# MCU.net
KiCad netlist of a schematic drawn in Altium Designer
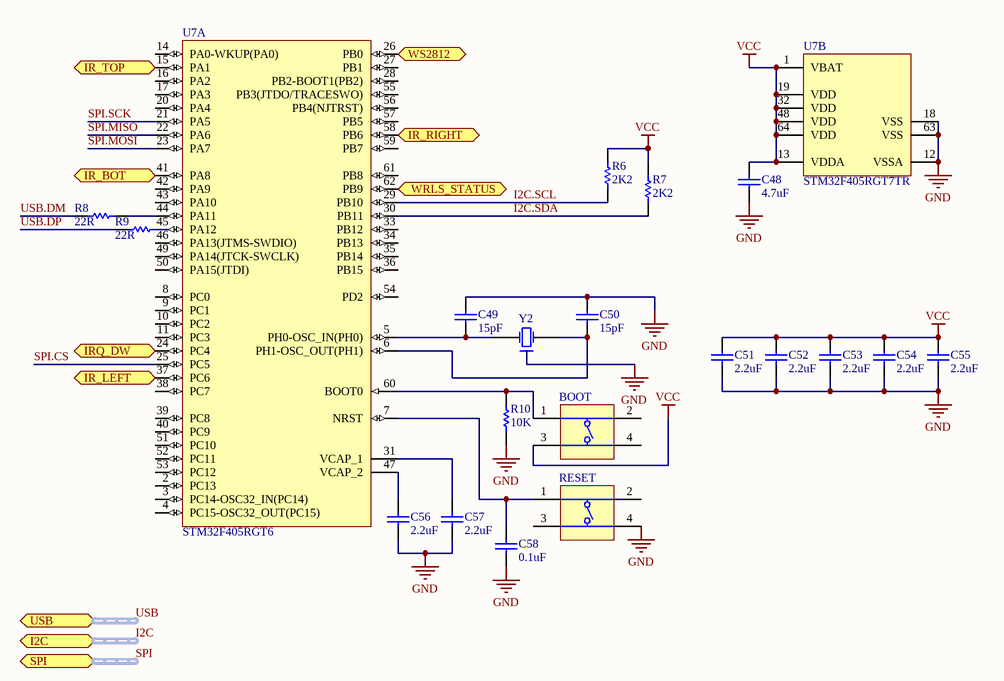
[diagram p0: MCU.SchDoc]

(export (version "E")
  (design (tool "Eeschema 10.0.6"))
  (components
    (comp (ref "BOOT")
      (value "~")
      (footprint "SWITCH")
      (description "Switch, SPNO Push Button SMD")
      (fields
        (field (name "MANUFACTURER") "C&K Components")
        (field (name "PARTNUMBER") "PTS810 SJM 250 SMTR LFS")
      )
      (libsource (lib "Components") (part "DIPT-DTSM-6"))
    )
    (comp (ref "C48")
      (value "4.7uF")
      (footprint "C0402[1005X55]")
      (description "4.7uF 6.3V 20% 0402 (1005 Metric)")
      (fields (field (name "TOLERANCE") "20%") (field (name "PARTNUMBER") "GRM155R60J475ME47D"))
      (libsource (lib "Capacitors") (part "CAP_4.7uF_6.3V_0402_20%"))
    )
    (comp (ref "C49")
      (value "15pF")
      (footprint "C0402[1005X55]")
      (description "15pF 50V 5% 0402 (1005 Metric)")
      (fields (field (name "TOLERANCE") "5%") (field (name "PARTNUMBER") "GRM1555C1H150JA01D"))
      (libsource (lib "Capacitors") (part "CAP_15pF_50V_0402_5%"))
    )
    (comp (ref "C50")
      (value "15pF")
      (footprint "C0402[1005X55]")
      (description "15pF 50V 5% 0402 (1005 Metric)")
      (fields (field (name "TOLERANCE") "5%") (field (name "PARTNUMBER") "GRM1555C1H150JA01D"))
      (libsource (lib "Capacitors") (part "CAP_15pF_50V_0402_5%"))
    )
    (comp (ref "C51")
      (value "2.2uF")
      (footprint "C0402[1005X55]")
      (description "2.2uF 6.3V 20% 0402 (1005 Metric)")
      (fields (field (name "TOLERANCE") "20%") (field (name "PARTNUMBER") "GRM155R60J225ME15D"))
      (libsource (lib "Capacitors") (part "CAP_2.2uF_6.3V_0402_20%"))
    )
    (comp (ref "C52")
      (value "2.2uF")
      (footprint "C0402[1005X55]")
      (description "2.2uF 6.3V 20% 0402 (1005 Metric)")
      (fields (field (name "TOLERANCE") "20%") (field (name "PARTNUMBER") "GRM155R60J225ME15D"))
      (libsource (lib "Capacitors") (part "CAP_2.2uF_6.3V_0402_20%"))
    )
    (comp (ref "C53")
      (value "2.2uF")
      (footprint "C0402[1005X55]")
      (description "2.2uF 6.3V 20% 0402 (1005 Metric)")
      (fields (field (name "TOLERANCE") "20%") (field (name "PARTNUMBER") "GRM155R60J225ME15D"))
      (libsource (lib "Capacitors") (part "CAP_2.2uF_6.3V_0402_20%"))
    )
    (comp (ref "C54")
      (value "2.2uF")
      (footprint "C0402[1005X55]")
      (description "2.2uF 6.3V 20% 0402 (1005 Metric)")
      (fields (field (name "TOLERANCE") "20%") (field (name "PARTNUMBER") "GRM155R60J225ME15D"))
      (libsource (lib "Capacitors") (part "CAP_2.2uF_6.3V_0402_20%"))
    )
    (comp (ref "C55")
      (value "2.2uF")
      (footprint "C0402[1005X55]")
      (description "2.2uF 6.3V 20% 0402 (1005 Metric)")
      (fields (field (name "TOLERANCE") "20%") (field (name "PARTNUMBER") "GRM155R60J225ME15D"))
      (libsource (lib "Capacitors") (part "CAP_2.2uF_6.3V_0402_20%"))
    )
    (comp (ref "C56")
      (value "2.2uF")
      (footprint "C0402[1005X55]")
      (description "2.2uF 6.3V 20% 0402 (1005 Metric)")
      (fields (field (name "TOLERANCE") "20%") (field (name "PARTNUMBER") "GRM155R60J225ME15D"))
      (libsource (lib "Capacitors") (part "CAP_2.2uF_6.3V_0402_20%"))
    )
    (comp (ref "C57")
      (value "2.2uF")
      (footprint "C0402[1005X55]")
      (description "2.2uF 6.3V 20% 0402 (1005 Metric)")
      (fields (field (name "TOLERANCE") "20%") (field (name "PARTNUMBER") "GRM155R60J225ME15D"))
      (libsource (lib "Capacitors") (part "CAP_2.2uF_6.3V_0402_20%"))
    )
    (comp (ref "C58")
      (value "0.1uF")
      (footprint "C0402[1005X55]")
      (description "0.1uF 6.3V 10% 0402 (1005 Metric)")
      (fields (field (name "TOLERANCE") "10%") (field (name "PARTNUMBER") "GRM155R70J104KA01D"))
      (libsource (lib "Capacitors") (part "CAP_0.1uF_6.3V_0402_10%"))
    )
    (comp (ref "R6")
      (value "2K2")
      (footprint "R0402[1005]")
      (description "2K2 0.063W 1% 0402 (1005 Metric)")
      (fields (field (name "TOLERANCE") "1%") (field (name "POWER") "0.063W"))
      (libsource (lib "Resistors") (part "RES_2K2_0402_1%"))
    )
    (comp (ref "R7")
      (value "2K2")
      (footprint "R0402[1005]")
      (description "2K2 0.063W 1% 0402 (1005 Metric)")
      (fields (field (name "TOLERANCE") "1%") (field (name "POWER") "0.063W"))
      (libsource (lib "Resistors") (part "RES_2K2_0402_1%"))
    )
    (comp (ref "R8")
      (value "22R")
      (footprint "R0402[1005]")
      (description "22R 0.063W 1% 0402 (1005 Metric)")
      (fields (field (name "POWER") "0.063W") (field (name "TOLERANCE") "1%"))
      (libsource (lib "Resistors") (part "RES_22R_0402_1%"))
    )
    (comp (ref "R9")
      (value "22R")
      (footprint "R0402[1005]")
      (description "22R 0.063W 1% 0402 (1005 Metric)")
      (fields (field (name "POWER") "0.063W") (field (name "TOLERANCE") "1%"))
      (libsource (lib "Resistors") (part "RES_22R_0402_1%"))
    )
    (comp (ref "R10")
      (value "10K")
      (footprint "R0402[1005]")
      (description "10K 0.063W 1% 0402 (1005 Metric)")
      (fields (field (name "TOLERANCE") "1%") (field (name "POWER") "0.063W"))
      (libsource (lib "Resistors") (part "RES_10K_0402_1%"))
    )
    (comp (ref "RESET")
      (value "~")
      (footprint "SWITCH")
      (description "Switch, SPNO Push Button SMD")
      (fields
        (field (name "MANUFACTURER") "C&K Components")
        (field (name "PARTNUMBER") "PTS810 SJM 250 SMTR LFS")
      )
      (libsource (lib "Components") (part "DIPT-DTSM-6"))
    )
    (comp (ref "U7")
      (value "STM32F405RGT7TR")
      (footprint "STM-LQFP64_V")
      (fields (field (name "MANUFACTURER") "STMicroelectronics"))
      (libsource (lib "Altium Content Vault") (part "CMP-0243-00089-2"))
    )
    (comp (ref "Y2")
      (value "~")
      (footprint "ABRA-ABM3B-4_V")
      (fields (field (name "PARTNUMBER") "ABM3B-8.000MHZ-10-1UT") (field (name "MANUFACTURER") "ABRACON"))
      (libsource (lib "Components") (part "ABRA-ABM3B-4"))
    )
  )
  (nets
    (net (code "4") (name "/I2C.SCL") (class "Default")
      (node (ref "R6") (pin "1") (pinfunction "1_1") (pintype "passive"))
      (node (ref "U7") (pin "29") (pinfunction "PB10_29") (pintype "bidirectional"))
    )
    (net (code "5") (name "/I2C.SDA") (class "Default")
      (node (ref "R7") (pin "1") (pinfunction "1_1") (pintype "passive"))
      (node (ref "U7") (pin "30") (pinfunction "PB11_30") (pintype "bidirectional"))
    )
    (net (code "6") (name "/IRQ_DW") (class "Default")
      (node (ref "U7") (pin "24") (pinfunction "PC4_24") (pintype "bidirectional"))
    )
    (net (code "7") (name "/IR_BOT") (class "Default")
      (node (ref "U7") (pin "41") (pinfunction "PA8_41") (pintype "bidirectional"))
    )
    (net (code "8") (name "/IR_LEFT") (class "Default")
      (node (ref "U7") (pin "37") (pinfunction "PC6_37") (pintype "bidirectional"))
    )
    (net (code "9") (name "/IR_RIGHT") (class "Default")
      (node (ref "U7") (pin "58") (pinfunction "PB6_58") (pintype "bidirectional"))
    )
    (net (code "10") (name "/IR_TOP") (class "Default")
      (node (ref "U7") (pin "15") (pinfunction "PA1_15") (pintype "bidirectional"))
    )
    (net (code "11") (name "/SPI.CS") (class "Default")
      (node (ref "U7") (pin "25") (pinfunction "PC5_25") (pintype "bidirectional"))
    )
    (net (code "12") (name "/SPI.MISO") (class "Default")
      (node (ref "U7") (pin "22") (pinfunction "PA6_22") (pintype "bidirectional"))
    )
    (net (code "13") (name "/SPI.MOSI") (class "Default")
      (node (ref "U7") (pin "23") (pinfunction "PA7_23") (pintype "bidirectional"))
    )
    (net (code "14") (name "/SPI.SCK") (class "Default")
      (node (ref "U7") (pin "21") (pinfunction "PA5_21") (pintype "bidirectional"))
    )
    (net (code "15") (name "/USB.DM") (class "Default")
      (node (ref "R8") (pin "1") (pinfunction "1_1") (pintype "passive"))
    )
    (net (code "16") (name "/USB.DP") (class "Default")
      (node (ref "R9") (pin "1") (pinfunction "1_1") (pintype "passive"))
    )
    (net (code "17") (name "/WRLS_STATUS") (class "Default")
      (node (ref "U7") (pin "62") (pinfunction "PB9_62") (pintype "bidirectional"))
    )
    (net (code "18") (name "/WS2812") (class "Default")
      (node (ref "U7") (pin "26") (pinfunction "PB0_26") (pintype "bidirectional"))
    )
    (net (code "22") (name "GND") (class "Default")
      (node (ref "C48") (pin "1") (pinfunction "1_1") (pintype "passive"))
      (node (ref "C49") (pin "2") (pinfunction "2_2") (pintype "passive"))
      (node (ref "C50") (pin "2") (pinfunction "2_2") (pintype "passive"))
      (node (ref "C51") (pin "1") (pinfunction "1_1") (pintype "passive"))
      (node (ref "C52") (pin "1") (pinfunction "1_1") (pintype "passive"))
      (node (ref "C53") (pin "1") (pinfunction "1_1") (pintype "passive"))
      (node (ref "C54") (pin "1") (pinfunction "1_1") (pintype "passive"))
      (node (ref "C55") (pin "1") (pinfunction "1_1") (pintype "passive"))
      (node (ref "C56") (pin "1") (pinfunction "1_1") (pintype "passive"))
      (node (ref "C57") (pin "1") (pinfunction "1_1") (pintype "passive"))
      (node (ref "C58") (pin "1") (pinfunction "1_1") (pintype "passive"))
      (node (ref "R10") (pin "1") (pinfunction "1_1") (pintype "passive"))
      (node (ref "RESET") (pin "4") (pinfunction "T3_4") (pintype "passive"))
      (node (ref "U7") (pin "12") (pinfunction "VSSA_12") (pintype "power_in"))
      (node (ref "U7") (pin "18") (pinfunction "VSS_18") (pintype "power_in"))
      (node (ref "U7") (pin "63") (pinfunction "VSS_63") (pintype "power_in"))
      (node (ref "Y2") (pin "2") (pinfunction "2_2") (pintype "passive"))
    )
    (net (code "23") (name "Net-(BOOT-T1)") (class "Default")
      (node (ref "BOOT") (pin "1") (pinfunction "T1_1") (pintype "passive"))
      (node (ref "R10") (pin "2") (pinfunction "2_2") (pintype "passive"))
      (node (ref "U7") (pin "60") (pinfunction "BOOT0_60") (pintype "input"))
    )
    (net (code "24") (name "Net-(RESET-T1)") (class "Default")
      (node (ref "C58") (pin "2") (pinfunction "2_2") (pintype "passive"))
      (node (ref "RESET") (pin "1") (pinfunction "T1_1") (pintype "passive"))
      (node (ref "U7") (pin "7") (pinfunction "NRST_7") (pintype "bidirectional"))
    )
    (net (code "25") (name "Net-(U7A-PA11)") (class "Default")
      (node (ref "R8") (pin "2") (pinfunction "2_2") (pintype "passive"))
      (node (ref "U7") (pin "44") (pinfunction "PA11_44") (pintype "bidirectional"))
    )
    (net (code "26") (name "Net-(U7A-PA12)") (class "Default")
      (node (ref "R9") (pin "2") (pinfunction "2_2") (pintype "passive"))
      (node (ref "U7") (pin "45") (pinfunction "PA12_45") (pintype "bidirectional"))
    )
    (net (code "27") (name "Net-(U7A-PH0-OSC_IN(PH0))") (class "Default")
      (node (ref "C49") (pin "1") (pinfunction "1_1") (pintype "passive"))
      (node (ref "U7") (pin "5") (pinfunction "PH0-OSC_IN(PH0)_5") (pintype "bidirectional"))
      (node (ref "Y2") (pin "3") (pinfunction "X2_3") (pintype "passive"))
    )
    (net (code "28") (name "Net-(U7A-PH1-OSC_OUT(PH1))") (class "Default")
      (node (ref "C50") (pin "1") (pinfunction "1_1") (pintype "passive"))
      (node (ref "U7") (pin "6") (pinfunction "PH1-OSC_OUT(PH1)_6") (pintype "bidirectional"))
      (node (ref "Y2") (pin "1") (pinfunction "X1_1") (pintype "passive"))
    )
    (net (code "29") (name "Net-(U7A-VCAP_1)") (class "Default")
      (node (ref "C57") (pin "2") (pinfunction "2_2") (pintype "passive"))
      (node (ref "U7") (pin "31") (pinfunction "VCAP_1_31") (pintype "power_in"))
    )
    (net (code "30") (name "Net-(U7A-VCAP_2)") (class "Default")
      (node (ref "C56") (pin "2") (pinfunction "2_2") (pintype "passive"))
      (node (ref "U7") (pin "47") (pinfunction "VCAP_2_47") (pintype "power_in"))
    )
    (net (code "31") (name "VCC") (class "Default")
      (node (ref "BOOT") (pin "3") (pinfunction "T3_3") (pintype "passive"))
      (node (ref "C48") (pin "2") (pinfunction "2_2") (pintype "passive"))
      (node (ref "C51") (pin "2") (pinfunction "2_2") (pintype "passive"))
      (node (ref "C52") (pin "2") (pinfunction "2_2") (pintype "passive"))
      (node (ref "C53") (pin "2") (pinfunction "2_2") (pintype "passive"))
      (node (ref "C54") (pin "2") (pinfunction "2_2") (pintype "passive"))
      (node (ref "C55") (pin "2") (pinfunction "2_2") (pintype "passive"))
      (node (ref "R6") (pin "2") (pinfunction "2_2") (pintype "passive"))
      (node (ref "R7") (pin "2") (pinfunction "2_2") (pintype "passive"))
      (node (ref "U7") (pin "1") (pinfunction "VBAT_1") (pintype "power_in"))
      (node (ref "U7") (pin "13") (pinfunction "VDDA_13") (pintype "power_in"))
      (node (ref "U7") (pin "19") (pinfunction "VDD_19") (pintype "power_in"))
      (node (ref "U7") (pin "32") (pinfunction "VDD_32") (pintype "power_in"))
      (node (ref "U7") (pin "48") (pinfunction "VDD_48") (pintype "power_in"))
      (node (ref "U7") (pin "64") (pinfunction "VDD_64") (pintype "power_in"))
    )
    (net (code "32") (name "unconnected-(BOOT-T2-Pad2)") (class "Default")
      (node (ref "BOOT") (pin "2") (pinfunction "T2_2") (pintype "passive"))
    )
    (net (code "33") (name "unconnected-(BOOT-T3-Pad4)") (class "Default")
      (node (ref "BOOT") (pin "4") (pinfunction "T3_4") (pintype "passive"))
    )
    (net (code "34") (name "unconnected-(RESET-T2-Pad2)") (class "Default")
      (node (ref "RESET") (pin "2") (pinfunction "T2_2") (pintype "passive"))
    )
    (net (code "35") (name "unconnected-(RESET-T3-Pad3)") (class "Default")
      (node (ref "RESET") (pin "3") (pinfunction "T3_3") (pintype "passive"))
    )
    (net (code "36") (name "unconnected-(U7A-PA0-WKUP(PA0)-Pad14)") (class "Default")
      (node (ref "U7") (pin "14") (pinfunction "PA0-WKUP(PA0)_14") (pintype "bidirectional"))
    )
    (net (code "37") (name "unconnected-(U7A-PA2-Pad16)") (class "Default")
      (node (ref "U7") (pin "16") (pinfunction "PA2_16") (pintype "bidirectional"))
    )
    (net (code "38") (name "unconnected-(U7A-PA3-Pad17)") (class "Default")
      (node (ref "U7") (pin "17") (pinfunction "PA3_17") (pintype "bidirectional"))
    )
    (net (code "39") (name "unconnected-(U7A-PA4-Pad20)") (class "Default")
      (node (ref "U7") (pin "20") (pinfunction "PA4_20") (pintype "bidirectional"))
    )
    (net (code "40") (name "unconnected-(U7A-PA9-Pad42)") (class "Default")
      (node (ref "U7") (pin "42") (pinfunction "PA9_42") (pintype "bidirectional"))
    )
    (net (code "41") (name "unconnected-(U7A-PA10-Pad43)") (class "Default")
      (node (ref "U7") (pin "43") (pinfunction "PA10_43") (pintype "bidirectional"))
    )
    (net (code "42") (name "unconnected-(U7A-PA13(JTMS-SWDIO)-Pad46)") (class "Default")
      (node (ref "U7") (pin "46") (pinfunction "PA13(JTMS-SWDIO)_46") (pintype "bidirectional"))
    )
    (net (code "43") (name "unconnected-(U7A-PA14(JTCK-SWCLK)-Pad49)") (class "Default")
      (node (ref "U7") (pin "49") (pinfunction "PA14(JTCK-SWCLK)_49") (pintype "bidirectional"))
    )
    (net (code "44") (name "unconnected-(U7A-PA15(JTDI)-Pad50)") (class "Default")
      (node (ref "U7") (pin "50") (pinfunction "PA15(JTDI)_50") (pintype "bidirectional"))
    )
    (net (code "45") (name "unconnected-(U7A-PB1-Pad27)") (class "Default")
      (node (ref "U7") (pin "27") (pinfunction "PB1_27") (pintype "bidirectional"))
    )
    (net (code "46") (name "unconnected-(U7A-PB2-BOOT1(PB2)-Pad28)") (class "Default")
      (node (ref "U7") (pin "28") (pinfunction "PB2-BOOT1(PB2)_28") (pintype "bidirectional"))
    )
    (net (code "47") (name "unconnected-(U7A-PB3(JTDO{slash}TRACESWO)-Pad55)") (class "Default")
      (node (ref "U7") (pin "55") (pinfunction "PB3(JTDO/TRACESWO)_55") (pintype "bidirectional"))
    )
    (net (code "48") (name "unconnected-(U7A-PB4(NJTRST)-Pad56)") (class "Default")
      (node (ref "U7") (pin "56") (pinfunction "PB4(NJTRST)_56") (pintype "bidirectional"))
    )
    (net (code "49") (name "unconnected-(U7A-PB5-Pad57)") (class "Default")
      (node (ref "U7") (pin "57") (pinfunction "PB5_57") (pintype "bidirectional"))
    )
    (net (code "50") (name "unconnected-(U7A-PB7-Pad59)") (class "Default")
      (node (ref "U7") (pin "59") (pinfunction "PB7_59") (pintype "bidirectional"))
    )
    (net (code "51") (name "unconnected-(U7A-PB8-Pad61)") (class "Default")
      (node (ref "U7") (pin "61") (pinfunction "PB8_61") (pintype "bidirectional"))
    )
    (net (code "52") (name "unconnected-(U7A-PB12-Pad33)") (class "Default")
      (node (ref "U7") (pin "33") (pinfunction "PB12_33") (pintype "bidirectional"))
    )
    (net (code "53") (name "unconnected-(U7A-PB13-Pad34)") (class "Default")
      (node (ref "U7") (pin "34") (pinfunction "PB13_34") (pintype "bidirectional"))
    )
    (net (code "54") (name "unconnected-(U7A-PB14-Pad35)") (class "Default")
      (node (ref "U7") (pin "35") (pinfunction "PB14_35") (pintype "bidirectional"))
    )
    (net (code "55") (name "unconnected-(U7A-PB15-Pad36)") (class "Default")
      (node (ref "U7") (pin "36") (pinfunction "PB15_36") (pintype "bidirectional"))
    )
    (net (code "56") (name "unconnected-(U7A-PC0-Pad8)") (class "Default")
      (node (ref "U7") (pin "8") (pinfunction "PC0_8") (pintype "bidirectional"))
    )
    (net (code "57") (name "unconnected-(U7A-PC1-Pad9)") (class "Default")
      (node (ref "U7") (pin "9") (pinfunction "PC1_9") (pintype "bidirectional"))
    )
    (net (code "58") (name "unconnected-(U7A-PC2-Pad10)") (class "Default")
      (node (ref "U7") (pin "10") (pinfunction "PC2_10") (pintype "bidirectional"))
    )
    (net (code "59") (name "unconnected-(U7A-PC3-Pad11)") (class "Default")
      (node (ref "U7") (pin "11") (pinfunction "PC3_11") (pintype "bidirectional"))
    )
    (net (code "60") (name "unconnected-(U7A-PC7-Pad38)") (class "Default")
      (node (ref "U7") (pin "38") (pinfunction "PC7_38") (pintype "bidirectional"))
    )
    (net (code "61") (name "unconnected-(U7A-PC8-Pad39)") (class "Default")
      (node (ref "U7") (pin "39") (pinfunction "PC8_39") (pintype "bidirectional"))
    )
    (net (code "62") (name "unconnected-(U7A-PC9-Pad40)") (class "Default")
      (node (ref "U7") (pin "40") (pinfunction "PC9_40") (pintype "bidirectional"))
    )
    (net (code "63") (name "unconnected-(U7A-PC10-Pad51)") (class "Default")
      (node (ref "U7") (pin "51") (pinfunction "PC10_51") (pintype "bidirectional"))
    )
    (net (code "64") (name "unconnected-(U7A-PC11-Pad52)") (class "Default")
      (node (ref "U7") (pin "52") (pinfunction "PC11_52") (pintype "bidirectional"))
    )
    (net (code "65") (name "unconnected-(U7A-PC12-Pad53)") (class "Default")
      (node (ref "U7") (pin "53") (pinfunction "PC12_53") (pintype "bidirectional"))
    )
    (net (code "66") (name "unconnected-(U7A-PC13-Pad2)") (class "Default")
      (node (ref "U7") (pin "2") (pinfunction "PC13_2") (pintype "bidirectional"))
    )
    (net (code "67") (name "unconnected-(U7A-PC14-OSC32_IN(PC14)-Pad3)") (class "Default")
      (node (ref "U7") (pin "3") (pinfunction "PC14-OSC32_IN(PC14)_3") (pintype "bidirectional"))
    )
    (net (code "68") (name "unconnected-(U7A-PC15-OSC32_OUT(PC15)-Pad4)") (class "Default")
      (node (ref "U7") (pin "4") (pinfunction "PC15-OSC32_OUT(PC15)_4") (pintype "bidirectional"))
    )
    (net (code "69") (name "unconnected-(U7A-PD2-Pad54)") (class "Default")
      (node (ref "U7") (pin "54") (pinfunction "PD2_54") (pintype "bidirectional"))
    )
  )
)
